# LEDs.net
KiCad netlist of a schematic drawn in Altium Designer
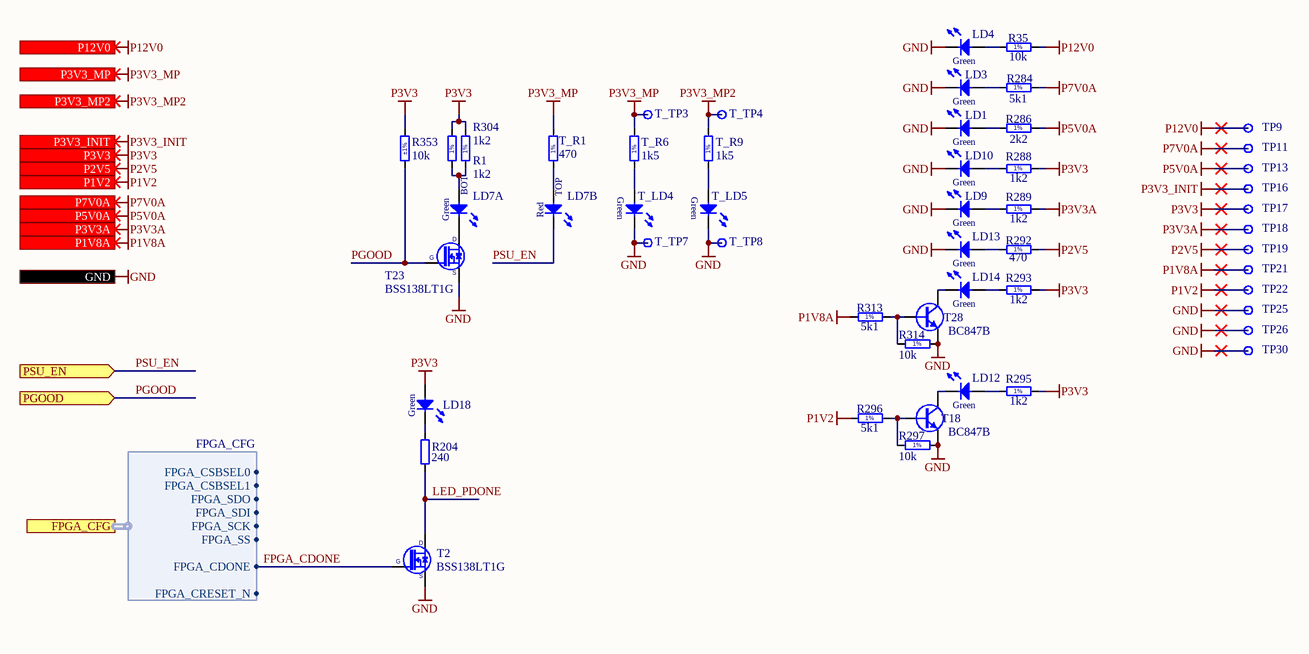
[diagram p0: LEDs.SchDoc]

(export (version "E")
  (design (tool "Eeschema 10.0.6"))
  (components
    (comp (ref "LD1")
      (value "Green")
      (footprint "LED_KINGBRIGHT_KPH-1608CGCK")
      (description "LED Green 1C 2A")
      (fields
        (field (name "PART NUMBER") "LED_KINGBRIGHT_KPH-1608CGCK")
        (field (name "MANUFACTURER") "KINGBRIGHT")
        (field (name "AUTHOR") "CERN DEM JLC")
      )
      (libsource (lib "ICs And Semiconductors") (part "LED Green 1C 2A"))
    )
    (comp (ref "LD3")
      (value "Green")
      (footprint "LED_KINGBRIGHT_KPH-1608CGCK")
      (description "LED Green 1C 2A")
      (fields
        (field (name "PART NUMBER") "LED_KINGBRIGHT_KPH-1608CGCK")
        (field (name "MANUFACTURER") "KINGBRIGHT")
        (field (name "AUTHOR") "CERN DEM JLC")
      )
      (libsource (lib "ICs And Semiconductors") (part "LED Green 1C 2A"))
    )
    (comp (ref "LD4")
      (value "Green")
      (footprint "LED_KINGBRIGHT_KPH-1608CGCK")
      (description "LED Green 1C 2A")
      (fields
        (field (name "PART NUMBER") "LED_KINGBRIGHT_KPH-1608CGCK")
        (field (name "MANUFACTURER") "KINGBRIGHT")
        (field (name "AUTHOR") "CERN DEM JLC")
      )
      (libsource (lib "ICs And Semiconductors") (part "LED Green 1C 2A"))
    )
    (comp (ref "LD7")
      (value "Red/Green")
      (footprint "LED_DIALIGHT_571-0112F")
      (description "2x LED  Botom Green, Top Red")
      (fields
        (field (name "PART NUMBER") "LED_DIALIGHT_571-0112F")
        (field (name "MANUFACTURER") "DIALIGHT")
        (field (name "AUTHOR") "CERN DEM JLC")
      )
      (libsource (lib "ICs And Semiconductors") (part "LED x2 G-1C2A-BOT_R-3C4A-TOP"))
    )
    (comp (ref "LD9")
      (value "Green")
      (footprint "LED_KINGBRIGHT_KPH-1608CGCK")
      (description "LED Green 1C 2A")
      (fields
        (field (name "PART NUMBER") "LED_KINGBRIGHT_KPH-1608CGCK")
        (field (name "MANUFACTURER") "KINGBRIGHT")
        (field (name "AUTHOR") "CERN DEM JLC")
      )
      (libsource (lib "ICs And Semiconductors") (part "LED Green 1C 2A"))
    )
    (comp (ref "LD10")
      (value "Green")
      (footprint "LED_KINGBRIGHT_KPH-1608CGCK")
      (description "LED Green 1C 2A")
      (fields
        (field (name "PART NUMBER") "LED_KINGBRIGHT_KPH-1608CGCK")
        (field (name "MANUFACTURER") "KINGBRIGHT")
        (field (name "AUTHOR") "CERN DEM JLC")
      )
      (libsource (lib "ICs And Semiconductors") (part "LED Green 1C 2A"))
    )
    (comp (ref "LD12")
      (value "Green")
      (footprint "LED_KINGBRIGHT_KPH-1608CGCK")
      (description "LED Green 1C 2A")
      (fields
        (field (name "PART NUMBER") "LED_KINGBRIGHT_KPH-1608CGCK")
        (field (name "MANUFACTURER") "KINGBRIGHT")
        (field (name "AUTHOR") "CERN DEM JLC")
      )
      (libsource (lib "ICs And Semiconductors") (part "LED Green 1C 2A"))
    )
    (comp (ref "LD13")
      (value "Green")
      (footprint "LED_KINGBRIGHT_KPH-1608CGCK")
      (description "LED Green 1C 2A")
      (fields
        (field (name "PART NUMBER") "LED_KINGBRIGHT_KPH-1608CGCK")
        (field (name "MANUFACTURER") "KINGBRIGHT")
        (field (name "AUTHOR") "CERN DEM JLC")
      )
      (libsource (lib "ICs And Semiconductors") (part "LED Green 1C 2A"))
    )
    (comp (ref "LD14")
      (value "Green")
      (footprint "LED_KINGBRIGHT_KPH-1608CGCK")
      (description "LED Green 1C 2A")
      (fields
        (field (name "PART NUMBER") "LED_KINGBRIGHT_KPH-1608CGCK")
        (field (name "MANUFACTURER") "KINGBRIGHT")
        (field (name "AUTHOR") "CERN DEM JLC")
      )
      (libsource (lib "ICs And Semiconductors") (part "LED Green 1C 2A"))
    )
    (comp (ref "LD18")
      (value "Green")
      (footprint "LED_AVAGO_HSME-C120")
      (description "LED Green 1C 2A")
      (fields
        (field (name "PART NUMBER") "LED_AVAGO_HSME-C120")
        (field (name "MANUFACTURER") "AVAGO TECHNOLOGIES")
        (field (name "AUTHOR") "CERN DEM JMW")
      )
      (libsource (lib "ICs And Semiconductors") (part "LED Green 1C 2A"))
    )
    (comp (ref "R1")
      (value "1k2")
      (footprint "RESC1608X55N")
      (description "Resistor - 1%")
      (fields
        (field (name "PART NUMBER") "R0603_1K2_1%_0.1W_100PPM")
        (field (name "POWER") "0.1W")
        (field (name "AUTHOR") "CERN DEM JLC")
      )
      (libsource (lib "Resistors") (part "Resistor - 1%"))
    )
    (comp (ref "R35")
      (value "10k")
      (footprint "RESC1005X40N")
      (description "Resistor - 1%")
      (fields
        (field (name "PART NUMBER") "R0402_10K_1%_0.0625W_100PPM")
        (field (name "POWER") "0.0625W")
        (field (name "AUTHOR") "CERN DEM JLC")
      )
      (libsource (lib "Resistors") (part "Resistor - 1%"))
    )
    (comp (ref "R204")
      (value "240")
      (footprint "RESC1005X40N")
      (description "Resistor - 1%")
      (fields
        (field (name "PART NUMBER") "R0402_240R_1%_0.0625W_100PPM")
        (field (name "POWER") "0.0625W")
        (field (name "AUTHOR") "CERN DEM JLC")
      )
      (libsource (lib "Resistors") (part "Resistor - 1%"))
    )
    (comp (ref "R284")
      (value "5k1")
      (footprint "RESC1005X40N")
      (description "Resistor - 1%")
      (fields
        (field (name "PART NUMBER") "R0402_5K1_1%_0.0625W_100PPM")
        (field (name "POWER") "0.0625W")
        (field (name "AUTHOR") "CERN DEM JLC")
      )
      (libsource (lib "Resistors") (part "Resistor - 1%"))
    )
    (comp (ref "R286")
      (value "2k2")
      (footprint "RESC1005X40N")
      (description "Resistor - 1%")
      (fields
        (field (name "PART NUMBER") "R0402_2K2_1%_0.0625W_100PPM")
        (field (name "POWER") "0.0625W")
        (field (name "AUTHOR") "CERN DEM JLC")
      )
      (libsource (lib "Resistors") (part "Resistor - 1%"))
    )
    (comp (ref "R288")
      (value "1k2")
      (footprint "RESC1608X55N")
      (description "Resistor - 1%")
      (fields
        (field (name "PART NUMBER") "R0603_1K2_1%_0.1W_100PPM")
        (field (name "POWER") "0.1W")
        (field (name "AUTHOR") "CERN DEM JLC")
      )
      (libsource (lib "Resistors") (part "Resistor - 1%"))
    )
    (comp (ref "R289")
      (value "1k2")
      (footprint "RESC1608X55N")
      (description "Resistor - 1%")
      (fields
        (field (name "PART NUMBER") "R0603_1K2_1%_0.1W_100PPM")
        (field (name "POWER") "0.1W")
        (field (name "AUTHOR") "CERN DEM JLC")
      )
      (libsource (lib "Resistors") (part "Resistor - 1%"))
    )
    (comp (ref "R292")
      (value "470")
      (footprint "RESC1005X40N")
      (description "Resistor - 1%")
      (fields
        (field (name "PART NUMBER") "R0402_470R_1%_0.0625W_100PPM")
        (field (name "POWER") "0.0625W")
        (field (name "AUTHOR") "CERN DEM JLC")
      )
      (libsource (lib "Resistors") (part "Resistor - 1%"))
    )
    (comp (ref "R293")
      (value "1k2")
      (footprint "RESC1608X55N")
      (description "Resistor - 1%")
      (fields
        (field (name "PART NUMBER") "R0603_1K2_1%_0.1W_100PPM")
        (field (name "POWER") "0.1W")
        (field (name "AUTHOR") "CERN DEM JLC")
      )
      (libsource (lib "Resistors") (part "Resistor - 1%"))
    )
    (comp (ref "R295")
      (value "1k2")
      (footprint "RESC1608X55N")
      (description "Resistor - 1%")
      (fields
        (field (name "PART NUMBER") "R0603_1K2_1%_0.1W_100PPM")
        (field (name "POWER") "0.1W")
        (field (name "AUTHOR") "CERN DEM JLC")
      )
      (libsource (lib "Resistors") (part "Resistor - 1%"))
    )
    (comp (ref "R296")
      (value "5k1")
      (footprint "RESC1005X40N")
      (description "Resistor - 1%")
      (fields
        (field (name "PART NUMBER") "R0402_5K1_1%_0.0625W_100PPM")
        (field (name "POWER") "0.0625W")
        (field (name "AUTHOR") "CERN DEM JLC")
      )
      (libsource (lib "Resistors") (part "Resistor - 1%"))
    )
    (comp (ref "R297")
      (value "10k")
      (footprint "RESC1005X40N")
      (description "Resistor - 1%")
      (fields
        (field (name "PART NUMBER") "R0402_10K_1%_0.0625W_100PPM")
        (field (name "POWER") "0.0625W")
        (field (name "AUTHOR") "CERN DEM JLC")
      )
      (libsource (lib "Resistors") (part "Resistor - 1%"))
    )
    (comp (ref "R304")
      (value "1k2")
      (footprint "RESC1608X55N")
      (description "Resistor - 1%")
      (fields
        (field (name "PART NUMBER") "R0603_1K2_1%_0.1W_100PPM")
        (field (name "POWER") "0.1W")
        (field (name "AUTHOR") "CERN DEM JLC")
      )
      (libsource (lib "Resistors") (part "Resistor - 1%"))
    )
    (comp (ref "R313")
      (value "5k1")
      (footprint "RESC1005X40N")
      (description "Resistor - 1%")
      (fields
        (field (name "PART NUMBER") "R0402_5K1_1%_0.0625W_100PPM")
        (field (name "POWER") "0.0625W")
        (field (name "AUTHOR") "CERN DEM JLC")
      )
      (libsource (lib "Resistors") (part "Resistor - 1%"))
    )
    (comp (ref "R314")
      (value "10k")
      (footprint "RESC1005X40N")
      (description "Resistor - 1%")
      (fields
        (field (name "PART NUMBER") "R0402_10K_1%_0.0625W_100PPM")
        (field (name "POWER") "0.0625W")
        (field (name "AUTHOR") "CERN DEM JLC")
      )
      (libsource (lib "Resistors") (part "Resistor - 1%"))
    )
    (comp (ref "R353")
      (value "10k")
      (footprint "RESC1005X40N")
      (description "Resistor - 1%")
      (fields
        (field (name "TOLERANCE") "±1%")
        (field (name "PART NUMBER") "R0402_10K_1%_0.0625W_100PPM")
        (field (name "POWER") "0.0625W")
        (field (name "AUTHOR") "CERN DEM JLC")
      )
      (libsource (lib "Resistors") (part "Resistor - 1%"))
    )
    (comp (ref "T2")
      (value "BSS138LT1G")
      (footprint "SOT95P240X110-3N")
      (description "N-CHANNEL MOSFET WITH DIODE")
      (fields (field (name "MANUFACTURER") "ON SEMICONDUCTOR") (field (name "AUTHOR") "CERN DEM JLC"))
      (libsource (lib "ICs And Semiconductors") (part "N-MOSFET-D 1G 2S 3D"))
    )
    (comp (ref "T18")
      (value "BC847B")
      (footprint "SOT95P230X110-3N")
      (description "NPN Transistor")
      (fields (field (name "MANUFACTURER") "NXP SEMICONDUCTORS") (field (name "AUTHOR") "CERN DEM JLC"))
      (libsource (lib "ICs And Semiconductors") (part "NPN B1 E2 C3"))
    )
    (comp (ref "T23")
      (value "BSS138LT1G")
      (footprint "SOT95P240X110-3N")
      (description "N-CHANNEL MOSFET WITH DIODE")
      (fields
        (field (name "MANUFACTURER") "ON SEMICONDUCTOR")
        (field (name "MANUFACTURER PART NUMBER") "BSS138L")
        (field (name "AUTHOR") "CERN DEM JLC")
      )
      (libsource (lib "ICs And Semiconductors") (part "N-MOSFET-D 1G 2S 3D"))
    )
    (comp (ref "T28")
      (value "BC847B")
      (footprint "SOT95P230X110-3N")
      (description "NPN Transistor")
      (fields (field (name "MANUFACTURER") "NXP SEMICONDUCTORS") (field (name "AUTHOR") "CERN DEM JLC"))
      (libsource (lib "ICs And Semiconductors") (part "NPN B1 E2 C3"))
    )
    (comp (ref "TP9")
      (value "Test Point")
      (footprint "TPS127")
      (fields (field (name "PART NUMBER") "SMD_PAD_1.27X1.27MM") (field (name "AUTHOR") "CERN DEM JLC"))
      (libsource (lib "Eletro-mechanical") (part "Test Point"))
    )
    (comp (ref "TP11")
      (value "Test Point")
      (footprint "TPS127")
      (fields (field (name "PART NUMBER") "SMD_PAD_1.27X1.27MM") (field (name "AUTHOR") "CERN DEM JLC"))
      (libsource (lib "Eletro-mechanical") (part "Test Point"))
    )
    (comp (ref "TP13")
      (value "Test Point")
      (footprint "TPS127")
      (fields (field (name "PART NUMBER") "SMD_PAD_1.27X1.27MM") (field (name "AUTHOR") "CERN DEM JLC"))
      (libsource (lib "Eletro-mechanical") (part "Test Point"))
    )
    (comp (ref "TP16")
      (value "Test Point")
      (footprint "TPS127")
      (fields (field (name "PART NUMBER") "SMD_PAD_1.27X1.27MM") (field (name "AUTHOR") "CERN DEM JLC"))
      (libsource (lib "Eletro-mechanical") (part "Test Point"))
    )
    (comp (ref "TP17")
      (value "Test Point")
      (footprint "TPS127")
      (fields (field (name "PART NUMBER") "SMD_PAD_1.27X1.27MM") (field (name "AUTHOR") "CERN DEM JLC"))
      (libsource (lib "Eletro-mechanical") (part "Test Point"))
    )
    (comp (ref "TP18")
      (value "Test Point")
      (footprint "TPS127")
      (fields (field (name "PART NUMBER") "SMD_PAD_1.27X1.27MM") (field (name "AUTHOR") "CERN DEM JLC"))
      (libsource (lib "Eletro-mechanical") (part "Test Point"))
    )
    (comp (ref "TP19")
      (value "Test Point")
      (footprint "TPS127")
      (fields (field (name "PART NUMBER") "SMD_PAD_1.27X1.27MM") (field (name "AUTHOR") "CERN DEM JLC"))
      (libsource (lib "Eletro-mechanical") (part "Test Point"))
    )
    (comp (ref "TP21")
      (value "Test Point")
      (footprint "TPS127")
      (fields (field (name "PART NUMBER") "SMD_PAD_1.27X1.27MM") (field (name "AUTHOR") "CERN DEM JLC"))
      (libsource (lib "Eletro-mechanical") (part "Test Point"))
    )
    (comp (ref "TP22")
      (value "Test Point")
      (footprint "TPS127")
      (fields (field (name "PART NUMBER") "SMD_PAD_1.27X1.27MM") (field (name "AUTHOR") "CERN DEM JLC"))
      (libsource (lib "Eletro-mechanical") (part "Test Point"))
    )
    (comp (ref "TP25")
      (value "Test Point")
      (footprint "TPS127")
      (fields (field (name "PART NUMBER") "SMD_PAD_1.27X1.27MM") (field (name "AUTHOR") "CERN DEM JLC"))
      (libsource (lib "Eletro-mechanical") (part "Test Point"))
    )
    (comp (ref "TP26")
      (value "Test Point")
      (footprint "TPS127")
      (fields (field (name "PART NUMBER") "SMD_PAD_1.27X1.27MM") (field (name "AUTHOR") "CERN DEM JLC"))
      (libsource (lib "Eletro-mechanical") (part "Test Point"))
    )
    (comp (ref "TP30")
      (value "Test Point")
      (footprint "TPS127")
      (fields (field (name "PART NUMBER") "SMD_PAD_1.27X1.27MM") (field (name "AUTHOR") "CERN DEM JLC"))
      (libsource (lib "Eletro-mechanical") (part "Test Point"))
    )
    (comp (ref "T_LD4")
      (value "Green")
      (footprint "LED_KINGBRIGHT_KPH-1608CGCK")
      (description "LED Green 1C 2A")
      (fields
        (field (name "PART NUMBER") "LED_KINGBRIGHT_KPH-1608CGCK")
        (field (name "MANUFACTURER") "KINGBRIGHT")
        (field (name "AUTHOR") "CERN DEM JLC")
      )
      (libsource (lib "") (part "LED Green 1C 2A_1"))
    )
    (comp (ref "T_LD5")
      (value "Green")
      (footprint "LED_KINGBRIGHT_KPH-1608CGCK")
      (description "LED Green 1C 2A")
      (fields
        (field (name "PART NUMBER") "LED_KINGBRIGHT_KPH-1608CGCK")
        (field (name "MANUFACTURER") "KINGBRIGHT")
        (field (name "AUTHOR") "CERN DEM JLC")
      )
      (libsource (lib "") (part "LED Green 1C 2A_1"))
    )
    (comp (ref "T_R1")
      (value "470")
      (footprint "RESC1005X40N")
      (description "Resistor - 1%")
      (fields
        (field (name "PART NUMBER") "R0402_470R_1%_0.0625W_100PPM")
        (field (name "POWER") "0.0625W")
        (field (name "AUTHOR") "CERN DEM JLC")
      )
      (libsource (lib "Resistors") (part "Resistor - 1%"))
    )
    (comp (ref "T_R6")
      (value "1k5")
      (footprint "RESC1608X55N")
      (description "Resistor - 1%")
      (fields
        (field (name "PART NUMBER") "R0603_1K5_1%_0.1W_100PPM")
        (field (name "POWER") "0.1W")
        (field (name "AUTHOR") "CERN DEM JLC")
      )
      (libsource (lib "Resistors") (part "Resistor - 1%"))
    )
    (comp (ref "T_R9")
      (value "1k5")
      (footprint "RESC1608X55N")
      (description "Resistor - 1%")
      (fields
        (field (name "PART NUMBER") "R0603_1K5_1%_0.1W_100PPM")
        (field (name "POWER") "0.1W")
        (field (name "AUTHOR") "CERN DEM JLC")
      )
      (libsource (lib "Resistors") (part "Resistor - 1%"))
    )
    (comp (ref "T_TP3")
      (value "Test Point")
      (footprint "TPS127")
      (fields (field (name "PART NUMBER") "SMD_PAD_1.27X1.27MM") (field (name "AUTHOR") "CERN DEM JLC"))
      (libsource (lib "Eletro-mechanical") (part "Test Point"))
    )
    (comp (ref "T_TP4")
      (value "Test Point")
      (footprint "TPS127")
      (fields (field (name "PART NUMBER") "SMD_PAD_1.27X1.27MM") (field (name "AUTHOR") "CERN DEM JLC"))
      (libsource (lib "Eletro-mechanical") (part "Test Point"))
    )
    (comp (ref "T_TP7")
      (value "Test Point")
      (footprint "TPS127")
      (fields (field (name "PART NUMBER") "SMD_PAD_1.27X1.27MM") (field (name "AUTHOR") "CERN DEM JLC"))
      (libsource (lib "Eletro-mechanical") (part "Test Point"))
    )
    (comp (ref "T_TP8")
      (value "Test Point")
      (footprint "TPS127")
      (fields (field (name "PART NUMBER") "SMD_PAD_1.27X1.27MM") (field (name "AUTHOR") "CERN DEM JLC"))
      (libsource (lib "Eletro-mechanical") (part "Test Point"))
    )
  )
  (nets
    (net (code "2") (name "/FPGA_CDONE") (class "Default")
      (node (ref "T2") (pin "1") (pinfunction "G_1") (pintype "passive"))
    )
    (net (code "3") (name "/LED_PDONE") (class "Default")
      (node (ref "R204") (pin "1") (pinfunction "1_1") (pintype "passive"))
      (node (ref "T2") (pin "3") (pinfunction "D_3") (pintype "passive"))
    )
    (net (code "4") (name "/PGOOD") (class "Default")
      (node (ref "R353") (pin "1") (pinfunction "1_1") (pintype "passive"))
      (node (ref "T23") (pin "1") (pinfunction "G_1") (pintype "passive"))
    )
    (net (code "5") (name "/PSU_EN") (class "Default")
      (node (ref "LD7") (pin "3") (pinfunction "C_3") (pintype "passive"))
    )
    (net (code "7") (name "GND") (class "Default")
      (node (ref "LD1") (pin "1") (pinfunction "C_1") (pintype "passive"))
      (node (ref "LD10") (pin "1") (pinfunction "C_1") (pintype "passive"))
      (node (ref "LD13") (pin "1") (pinfunction "C_1") (pintype "passive"))
      (node (ref "LD3") (pin "1") (pinfunction "C_1") (pintype "passive"))
      (node (ref "LD4") (pin "1") (pinfunction "C_1") (pintype "passive"))
      (node (ref "LD9") (pin "1") (pinfunction "C_1") (pintype "passive"))
      (node (ref "R297") (pin "2") (pinfunction "2_2") (pintype "passive"))
      (node (ref "R314") (pin "2") (pinfunction "2_2") (pintype "passive"))
      (node (ref "T18") (pin "2") (pinfunction "E_2") (pintype "passive"))
      (node (ref "T2") (pin "2") (pinfunction "S_2") (pintype "passive"))
      (node (ref "T23") (pin "2") (pinfunction "S_2") (pintype "passive"))
      (node (ref "T28") (pin "2") (pinfunction "E_2") (pintype "passive"))
      (node (ref "TP25") (pin "1") (pinfunction "1_1") (pintype "bidirectional"))
      (node (ref "TP26") (pin "1") (pinfunction "1_1") (pintype "bidirectional"))
      (node (ref "TP30") (pin "1") (pinfunction "1_1") (pintype "bidirectional"))
      (node (ref "T_LD4") (pin "1") (pinfunction "C_1") (pintype "passive"))
      (node (ref "T_LD5") (pin "1") (pinfunction "C_1") (pintype "passive"))
      (node (ref "T_TP7") (pin "1") (pinfunction "1_1") (pintype "bidirectional"))
      (node (ref "T_TP8") (pin "1") (pinfunction "1_1") (pintype "bidirectional"))
    )
    (net (code "8") (name "Net-(LD1-A)") (class "Default")
      (node (ref "LD1") (pin "2") (pinfunction "A_2") (pintype "passive"))
      (node (ref "R286") (pin "1") (pinfunction "1_1") (pintype "passive"))
    )
    (net (code "9") (name "Net-(LD3-A)") (class "Default")
      (node (ref "LD3") (pin "2") (pinfunction "A_2") (pintype "passive"))
      (node (ref "R284") (pin "1") (pinfunction "1_1") (pintype "passive"))
    )
    (net (code "10") (name "Net-(LD4-A)") (class "Default")
      (node (ref "LD4") (pin "2") (pinfunction "A_2") (pintype "passive"))
      (node (ref "R35") (pin "1") (pinfunction "1_1") (pintype "passive"))
    )
    (net (code "11") (name "Net-(LD7A-A)") (class "Default")
      (node (ref "LD7") (pin "2") (pinfunction "A_2") (pintype "passive"))
      (node (ref "R1") (pin "1") (pinfunction "1_1") (pintype "passive"))
      (node (ref "R304") (pin "1") (pinfunction "1_1") (pintype "passive"))
    )
    (net (code "12") (name "Net-(LD7A-C)") (class "Default")
      (node (ref "LD7") (pin "1") (pinfunction "C_1") (pintype "passive"))
      (node (ref "T23") (pin "3") (pinfunction "D_3") (pintype "passive"))
    )
    (net (code "13") (name "Net-(LD7B-A)") (class "Default")
      (node (ref "LD7") (pin "4") (pinfunction "A_4") (pintype "passive"))
      (node (ref "T_R1") (pin "2") (pinfunction "2_2") (pintype "passive"))
    )
    (net (code "14") (name "Net-(LD9-A)") (class "Default")
      (node (ref "LD9") (pin "2") (pinfunction "A_2") (pintype "passive"))
      (node (ref "R289") (pin "1") (pinfunction "1_1") (pintype "passive"))
    )
    (net (code "15") (name "Net-(LD10-A)") (class "Default")
      (node (ref "LD10") (pin "2") (pinfunction "A_2") (pintype "passive"))
      (node (ref "R288") (pin "1") (pinfunction "1_1") (pintype "passive"))
    )
    (net (code "16") (name "Net-(LD12-A)") (class "Default")
      (node (ref "LD12") (pin "2") (pinfunction "A_2") (pintype "passive"))
      (node (ref "R295") (pin "1") (pinfunction "1_1") (pintype "passive"))
    )
    (net (code "17") (name "Net-(LD12-C)") (class "Default")
      (node (ref "LD12") (pin "1") (pinfunction "C_1") (pintype "passive"))
      (node (ref "T18") (pin "3") (pinfunction "C_3") (pintype "passive"))
    )
    (net (code "18") (name "Net-(LD13-A)") (class "Default")
      (node (ref "LD13") (pin "2") (pinfunction "A_2") (pintype "passive"))
      (node (ref "R292") (pin "2") (pinfunction "2_2") (pintype "passive"))
    )
    (net (code "19") (name "Net-(LD14-A)") (class "Default")
      (node (ref "LD14") (pin "2") (pinfunction "A_2") (pintype "passive"))
      (node (ref "R293") (pin "1") (pinfunction "1_1") (pintype "passive"))
    )
    (net (code "20") (name "Net-(LD14-C)") (class "Default")
      (node (ref "LD14") (pin "1") (pinfunction "C_1") (pintype "passive"))
      (node (ref "T28") (pin "3") (pinfunction "C_3") (pintype "passive"))
    )
    (net (code "21") (name "Net-(LD18-C)") (class "Default")
      (node (ref "LD18") (pin "1") (pinfunction "C_1") (pintype "passive"))
      (node (ref "R204") (pin "2") (pinfunction "2_2") (pintype "passive"))
    )
    (net (code "22") (name "Net-(T18-B)") (class "Default")
      (node (ref "R296") (pin "2") (pinfunction "2_2") (pintype "passive"))
      (node (ref "R297") (pin "1") (pinfunction "1_1") (pintype "passive"))
      (node (ref "T18") (pin "1") (pinfunction "B_1") (pintype "passive"))
    )
    (net (code "23") (name "Net-(T28-B)") (class "Default")
      (node (ref "R313") (pin "2") (pinfunction "2_2") (pintype "passive"))
      (node (ref "R314") (pin "1") (pinfunction "1_1") (pintype "passive"))
      (node (ref "T28") (pin "1") (pinfunction "B_1") (pintype "passive"))
    )
    (net (code "24") (name "Net-(T_LD4-A)") (class "Default")
      (node (ref "T_LD4") (pin "2") (pinfunction "A_2") (pintype "passive"))
      (node (ref "T_R6") (pin "1") (pinfunction "1_1") (pintype "passive"))
    )
    (net (code "25") (name "Net-(T_LD5-A)") (class "Default")
      (node (ref "T_LD5") (pin "2") (pinfunction "A_2") (pintype "passive"))
      (node (ref "T_R9") (pin "1") (pinfunction "1_1") (pintype "passive"))
    )
    (net (code "26") (name "P1V2") (class "Default")
      (node (ref "R296") (pin "1") (pinfunction "1_1") (pintype "passive"))
      (node (ref "TP22") (pin "1") (pinfunction "1_1") (pintype "bidirectional"))
    )
    (net (code "27") (name "P1V8A") (class "Default")
      (node (ref "R313") (pin "1") (pinfunction "1_1") (pintype "passive"))
      (node (ref "TP21") (pin "1") (pinfunction "1_1") (pintype "bidirectional"))
    )
    (net (code "28") (name "P2V5") (class "Default")
      (node (ref "R292") (pin "1") (pinfunction "1_1") (pintype "passive"))
      (node (ref "TP19") (pin "1") (pinfunction "1_1") (pintype "bidirectional"))
    )
    (net (code "29") (name "P3V3") (class "Default")
      (node (ref "LD18") (pin "2") (pinfunction "A_2") (pintype "passive"))
      (node (ref "R1") (pin "2") (pinfunction "2_2") (pintype "passive"))
      (node (ref "R288") (pin "2") (pinfunction "2_2") (pintype "passive"))
      (node (ref "R293") (pin "2") (pinfunction "2_2") (pintype "passive"))
      (node (ref "R295") (pin "2") (pinfunction "2_2") (pintype "passive"))
      (node (ref "R304") (pin "2") (pinfunction "2_2") (pintype "passive"))
      (node (ref "R353") (pin "2") (pinfunction "2_2") (pintype "passive"))
      (node (ref "TP17") (pin "1") (pinfunction "1_1") (pintype "bidirectional"))
    )
    (net (code "30") (name "P3V3A") (class "Default")
      (node (ref "R289") (pin "2") (pinfunction "2_2") (pintype "passive"))
      (node (ref "TP18") (pin "1") (pinfunction "1_1") (pintype "bidirectional"))
    )
    (net (code "31") (name "P3V3_INIT") (class "Default")
      (node (ref "TP16") (pin "1") (pinfunction "1_1") (pintype "bidirectional"))
    )
    (net (code "32") (name "P3V3_MP") (class "Default")
      (node (ref "T_R1") (pin "1") (pinfunction "1_1") (pintype "passive"))
      (node (ref "T_R6") (pin "2") (pinfunction "2_2") (pintype "passive"))
      (node (ref "T_TP3") (pin "1") (pinfunction "1_1") (pintype "bidirectional"))
    )
    (net (code "33") (name "P3V3_MP2") (class "Default")
      (node (ref "T_R9") (pin "2") (pinfunction "2_2") (pintype "passive"))
      (node (ref "T_TP4") (pin "1") (pinfunction "1_1") (pintype "bidirectional"))
    )
    (net (code "34") (name "P5V0A") (class "Default")
      (node (ref "R286") (pin "2") (pinfunction "2_2") (pintype "passive"))
      (node (ref "TP13") (pin "1") (pinfunction "1_1") (pintype "bidirectional"))
    )
    (net (code "35") (name "P7V0A") (class "Default")
      (node (ref "R284") (pin "2") (pinfunction "2_2") (pintype "passive"))
      (node (ref "TP11") (pin "1") (pinfunction "1_1") (pintype "bidirectional"))
    )
    (net (code "36") (name "P12V0") (class "Default")
      (node (ref "R35") (pin "2") (pinfunction "2_2") (pintype "passive"))
      (node (ref "TP9") (pin "1") (pinfunction "1_1") (pintype "bidirectional"))
    )
  )
)
